# akabeacon_square_type2_MDBT40.net
KiCad netlist of a schematic drawn in EAGLE
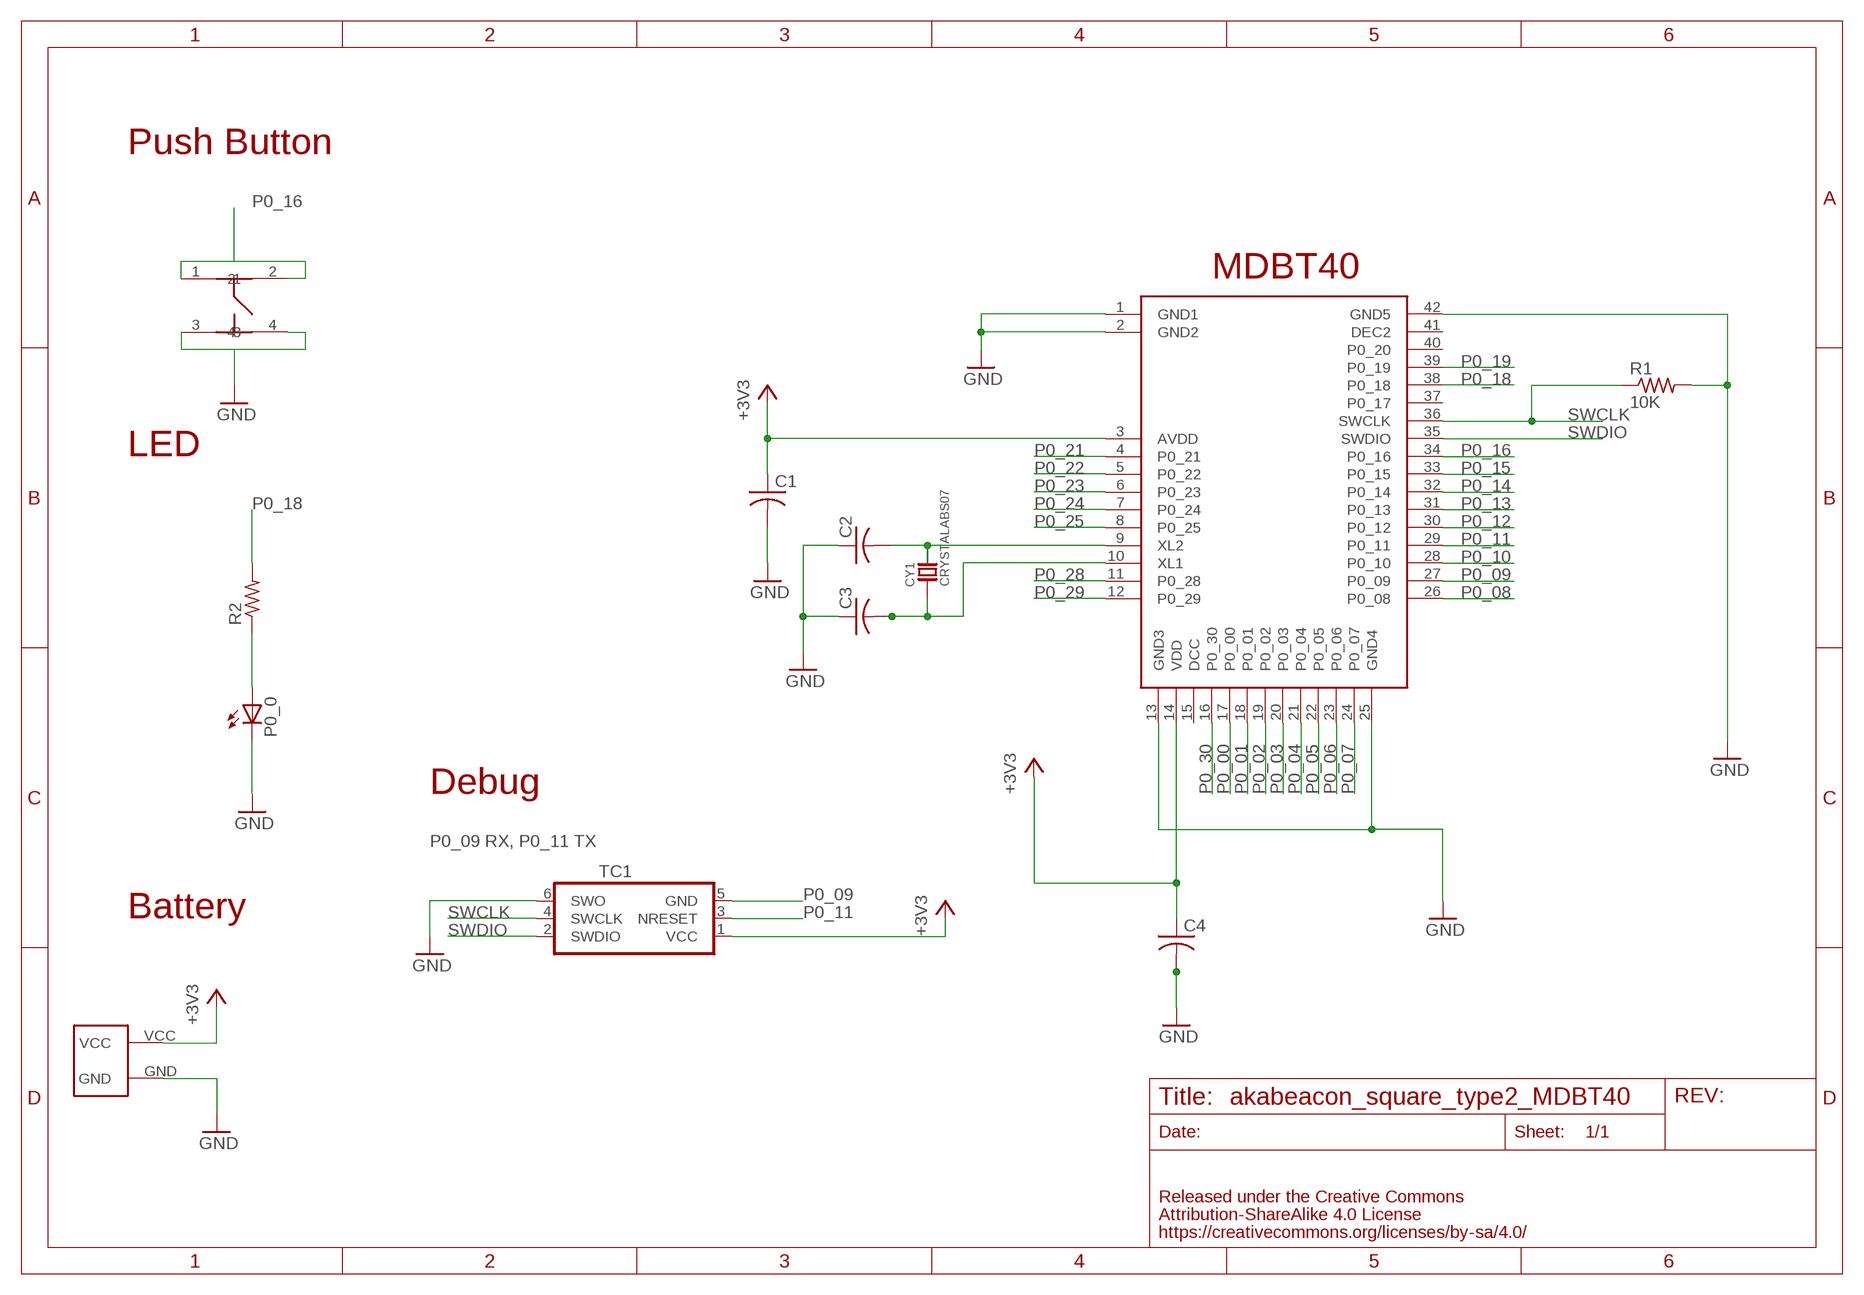
[diagram p0: schematic, sheet 1]

(export (version "E")
  (design (tool "Eeschema 10.0.6"))
  (components
    (comp (ref "C1")
      (value "C-USC0603")
      (footprint "eagle-import:C0603")
      (libsource (lib "eagle-import") (part "C-USC0603"))
    )
    (comp (ref "C2")
      (value "C-USC0603")
      (footprint "eagle-import:C0603")
      (libsource (lib "eagle-import") (part "C-USC0603"))
    )
    (comp (ref "C3")
      (value "C-USC0603")
      (footprint "eagle-import:C0603")
      (libsource (lib "eagle-import") (part "C-USC0603"))
    )
    (comp (ref "C4")
      (value "C-USC0603")
      (footprint "eagle-import:C0603")
      (libsource (lib "eagle-import") (part "C-USC0603"))
    )
    (comp (ref "CY1")
      (value "CRYSTALABS07")
      (footprint "eagle-import:ABRACOM-ABS07-32.768KHZ")
      (libsource (lib "eagle-import") (part "CRYSTALABS07"))
    )
    (comp (ref "P0_0")
      (value "LEDCHIP-LED0603")
      (footprint "eagle-import:CHIP-LED0603")
      (libsource (lib "eagle-import") (part "LEDCHIP-LED0603"))
    )
    (comp (ref "R1")
      (value "10K")
      (footprint "eagle-import:R0603")
      (libsource (lib "eagle-import") (part "R-US_R0603"))
    )
    (comp (ref "R2")
      (value "R-US_R0603")
      (footprint "eagle-import:R0603")
      (libsource (lib "eagle-import") (part "R-US_R0603"))
    )
    (comp (ref "TC1")
      (value "TC2030-IDC-NL")
      (footprint "eagle-import:TC2030-IDC-NL")
      (libsource (lib "eagle-import") (part "TC2030-IDC-NL"))
    )
    (comp (ref "U$2")
      (value "SQUARE-TYPE2-TC2030")
      (footprint "eagle-import:SQUARE-TYPE2-TC2030")
      (libsource (lib "eagle-import") (part "SQUARE-TYPE2-TC2030"))
    )
    (comp (ref "U$3")
      (value "RAYTAC-MDBT40")
      (footprint "eagle-import:RAYTAC-MDBT40")
      (libsource (lib "eagle-import") (part "RAYTAC-MDBT40"))
    )
    (comp (ref "U$6")
      (value "SWICTH-4P(KMR2)")
      (footprint "eagle-import:SWITCH-4P(KMR2)")
      (libsource (lib "eagle-import") (part "SWICTH-4P(KMR2)"))
    )
  )
  (nets
    (net (code "1") (name "+3V3") (class "Default")
      (node (ref "C1") (pin "1") (pinfunction "1_1") (pintype "passive"))
      (node (ref "C4") (pin "1") (pinfunction "1_1") (pintype "passive"))
      (node (ref "TC1") (pin "1") (pinfunction "VCC_1") (pintype "passive"))
      (node (ref "U$2") (pin "VCC") (pinfunction "VCC_VCC") (pintype "bidirectional"))
      (node (ref "U$3") (pin "14") (pinfunction "VDD_14") (pintype "bidirectional"))
      (node (ref "U$3") (pin "3") (pinfunction "AVDD_3") (pintype "bidirectional"))
    )
    (net (code "2") (name "/P0_00") (class "Default")
      (node (ref "U$3") (pin "17") (pinfunction "P0_00_17") (pintype "bidirectional"))
    )
    (net (code "3") (name "/P0_01") (class "Default")
      (node (ref "U$3") (pin "18") (pinfunction "P0_01_18") (pintype "bidirectional"))
    )
    (net (code "4") (name "/P0_02") (class "Default")
      (node (ref "U$3") (pin "19") (pinfunction "P0_02_19") (pintype "bidirectional"))
    )
    (net (code "5") (name "/P0_03") (class "Default")
      (node (ref "U$3") (pin "20") (pinfunction "P0_03_20") (pintype "bidirectional"))
    )
    (net (code "6") (name "/P0_04") (class "Default")
      (node (ref "U$3") (pin "21") (pinfunction "P0_04_21") (pintype "bidirectional"))
    )
    (net (code "7") (name "/P0_05") (class "Default")
      (node (ref "U$3") (pin "22") (pinfunction "P0_05_22") (pintype "bidirectional"))
    )
    (net (code "8") (name "/P0_06") (class "Default")
      (node (ref "U$3") (pin "23") (pinfunction "P0_06_23") (pintype "bidirectional"))
    )
    (net (code "9") (name "/P0_07") (class "Default")
      (node (ref "U$3") (pin "24") (pinfunction "P0_07_24") (pintype "bidirectional"))
    )
    (net (code "10") (name "/P0_08") (class "Default")
      (node (ref "U$3") (pin "26") (pinfunction "P0_08_26") (pintype "bidirectional"))
    )
    (net (code "11") (name "/P0_09") (class "Default")
      (node (ref "TC1") (pin "5") (pinfunction "GND_5") (pintype "passive"))
      (node (ref "U$3") (pin "27") (pinfunction "P0_09_27") (pintype "bidirectional"))
    )
    (net (code "12") (name "/P0_10") (class "Default")
      (node (ref "U$3") (pin "28") (pinfunction "P0_10_28") (pintype "bidirectional"))
    )
    (net (code "13") (name "/P0_11") (class "Default")
      (node (ref "TC1") (pin "3") (pinfunction "NRESET_3") (pintype "passive"))
      (node (ref "U$3") (pin "29") (pinfunction "P0_11_29") (pintype "bidirectional"))
    )
    (net (code "14") (name "/P0_12") (class "Default")
      (node (ref "U$3") (pin "30") (pinfunction "P0_12_30") (pintype "bidirectional"))
    )
    (net (code "15") (name "/P0_13") (class "Default")
      (node (ref "U$3") (pin "31") (pinfunction "P0_13_31") (pintype "bidirectional"))
    )
    (net (code "16") (name "/P0_14") (class "Default")
      (node (ref "U$3") (pin "32") (pinfunction "P0_14_32") (pintype "bidirectional"))
    )
    (net (code "17") (name "/P0_15") (class "Default")
      (node (ref "U$3") (pin "33") (pinfunction "P0_15_33") (pintype "bidirectional"))
    )
    (net (code "18") (name "/P0_16") (class "Default")
      (node (ref "U$3") (pin "34") (pinfunction "P0_16_34") (pintype "bidirectional"))
      (node (ref "U$6") (pin "1") (pinfunction "1_1") (pintype "bidirectional"))
      (node (ref "U$6") (pin "2") (pinfunction "2_2") (pintype "bidirectional"))
    )
    (net (code "19") (name "/P0_18") (class "Default")
      (node (ref "R2") (pin "2") (pinfunction "2_2") (pintype "passive"))
      (node (ref "U$3") (pin "38") (pinfunction "P0_18_38") (pintype "bidirectional"))
    )
    (net (code "20") (name "/P0_19") (class "Default")
      (node (ref "U$3") (pin "39") (pinfunction "P0_19_39") (pintype "bidirectional"))
    )
    (net (code "21") (name "/P0_21") (class "Default")
      (node (ref "U$3") (pin "4") (pinfunction "P0_21_4") (pintype "bidirectional"))
    )
    (net (code "22") (name "/P0_22") (class "Default")
      (node (ref "U$3") (pin "5") (pinfunction "P0_22_5") (pintype "bidirectional"))
    )
    (net (code "23") (name "/P0_23") (class "Default")
      (node (ref "U$3") (pin "6") (pinfunction "P0_23_6") (pintype "bidirectional"))
    )
    (net (code "24") (name "/P0_24") (class "Default")
      (node (ref "U$3") (pin "7") (pinfunction "P0_24_7") (pintype "bidirectional"))
    )
    (net (code "25") (name "/P0_25") (class "Default")
      (node (ref "U$3") (pin "8") (pinfunction "P0_25_8") (pintype "bidirectional"))
    )
    (net (code "26") (name "/P0_28") (class "Default")
      (node (ref "U$3") (pin "11") (pinfunction "P0_28_11") (pintype "bidirectional"))
    )
    (net (code "27") (name "/P0_29") (class "Default")
      (node (ref "U$3") (pin "12") (pinfunction "P0_29_12") (pintype "bidirectional"))
    )
    (net (code "28") (name "/P0_30") (class "Default")
      (node (ref "U$3") (pin "16") (pinfunction "P0_30_16") (pintype "bidirectional"))
    )
    (net (code "29") (name "/SWCLK") (class "Default")
      (node (ref "R1") (pin "1") (pinfunction "1_1") (pintype "passive"))
      (node (ref "TC1") (pin "4") (pinfunction "SWCLK_4") (pintype "passive"))
      (node (ref "U$3") (pin "36") (pinfunction "SWCLK_36") (pintype "bidirectional"))
    )
    (net (code "30") (name "/SWDIO") (class "Default")
      (node (ref "TC1") (pin "2") (pinfunction "SWDIO_2") (pintype "passive"))
      (node (ref "U$3") (pin "35") (pinfunction "SWDIO_35") (pintype "bidirectional"))
    )
    (net (code "31") (name "GND") (class "Default")
      (node (ref "C1") (pin "2") (pinfunction "2_2") (pintype "passive"))
      (node (ref "C2") (pin "1") (pinfunction "1_1") (pintype "passive"))
      (node (ref "C3") (pin "1") (pinfunction "1_1") (pintype "passive"))
      (node (ref "C4") (pin "2") (pinfunction "2_2") (pintype "passive"))
      (node (ref "P0_0") (pin "C") (pinfunction "C_C") (pintype "passive"))
      (node (ref "R1") (pin "2") (pinfunction "2_2") (pintype "passive"))
      (node (ref "TC1") (pin "6") (pinfunction "SWO_6") (pintype "passive"))
      (node (ref "U$2") (pin "GND") (pinfunction "GND_GND") (pintype "bidirectional"))
      (node (ref "U$3") (pin "1") (pinfunction "GND1_1") (pintype "bidirectional"))
      (node (ref "U$3") (pin "13") (pinfunction "GND3_13") (pintype "bidirectional"))
      (node (ref "U$3") (pin "2") (pinfunction "GND2_2") (pintype "bidirectional"))
      (node (ref "U$3") (pin "25") (pinfunction "GND4_25") (pintype "bidirectional"))
      (node (ref "U$3") (pin "42") (pinfunction "GND5_42") (pintype "bidirectional"))
      (node (ref "U$6") (pin "3") (pinfunction "3_3") (pintype "bidirectional"))
      (node (ref "U$6") (pin "4") (pinfunction "4_4") (pintype "bidirectional"))
    )
    (net (code "32") (name "Net-(P0_0-PadA)") (class "Default")
      (node (ref "P0_0") (pin "A") (pinfunction "A_A") (pintype "passive"))
      (node (ref "R2") (pin "1") (pinfunction "1_1") (pintype "passive"))
    )
    (net (code "33") (name "Net-(U$3-XL1)") (class "Default")
      (node (ref "C3") (pin "2") (pinfunction "2_2") (pintype "passive"))
      (node (ref "CY1") (pin "P$1") (pinfunction "P$1_P$1") (pintype "bidirectional"))
      (node (ref "U$3") (pin "10") (pinfunction "XL1_10") (pintype "bidirectional"))
    )
    (net (code "34") (name "Net-(U$3-XL2)") (class "Default")
      (node (ref "C2") (pin "2") (pinfunction "2_2") (pintype "passive"))
      (node (ref "CY1") (pin "P$2") (pinfunction "P$2_P$2") (pintype "bidirectional"))
      (node (ref "U$3") (pin "9") (pinfunction "XL2_9") (pintype "bidirectional"))
    )
    (net (code "35") (name "unconnected-(U$3-DCC-Pad15)") (class "Default")
      (node (ref "U$3") (pin "15") (pinfunction "DCC_15") (pintype "bidirectional"))
    )
    (net (code "36") (name "unconnected-(U$3-DEC2-Pad41)") (class "Default")
      (node (ref "U$3") (pin "41") (pinfunction "DEC2_41") (pintype "bidirectional"))
    )
    (net (code "37") (name "unconnected-(U$3-P0_17-Pad37)") (class "Default")
      (node (ref "U$3") (pin "37") (pinfunction "P0_17_37") (pintype "bidirectional"))
    )
    (net (code "38") (name "unconnected-(U$3-P0_20-Pad40)") (class "Default")
      (node (ref "U$3") (pin "40") (pinfunction "P0_20_40") (pintype "bidirectional"))
    )
  )
)
